# GSM.net
KiCad netlist of a schematic drawn in Altium Designer
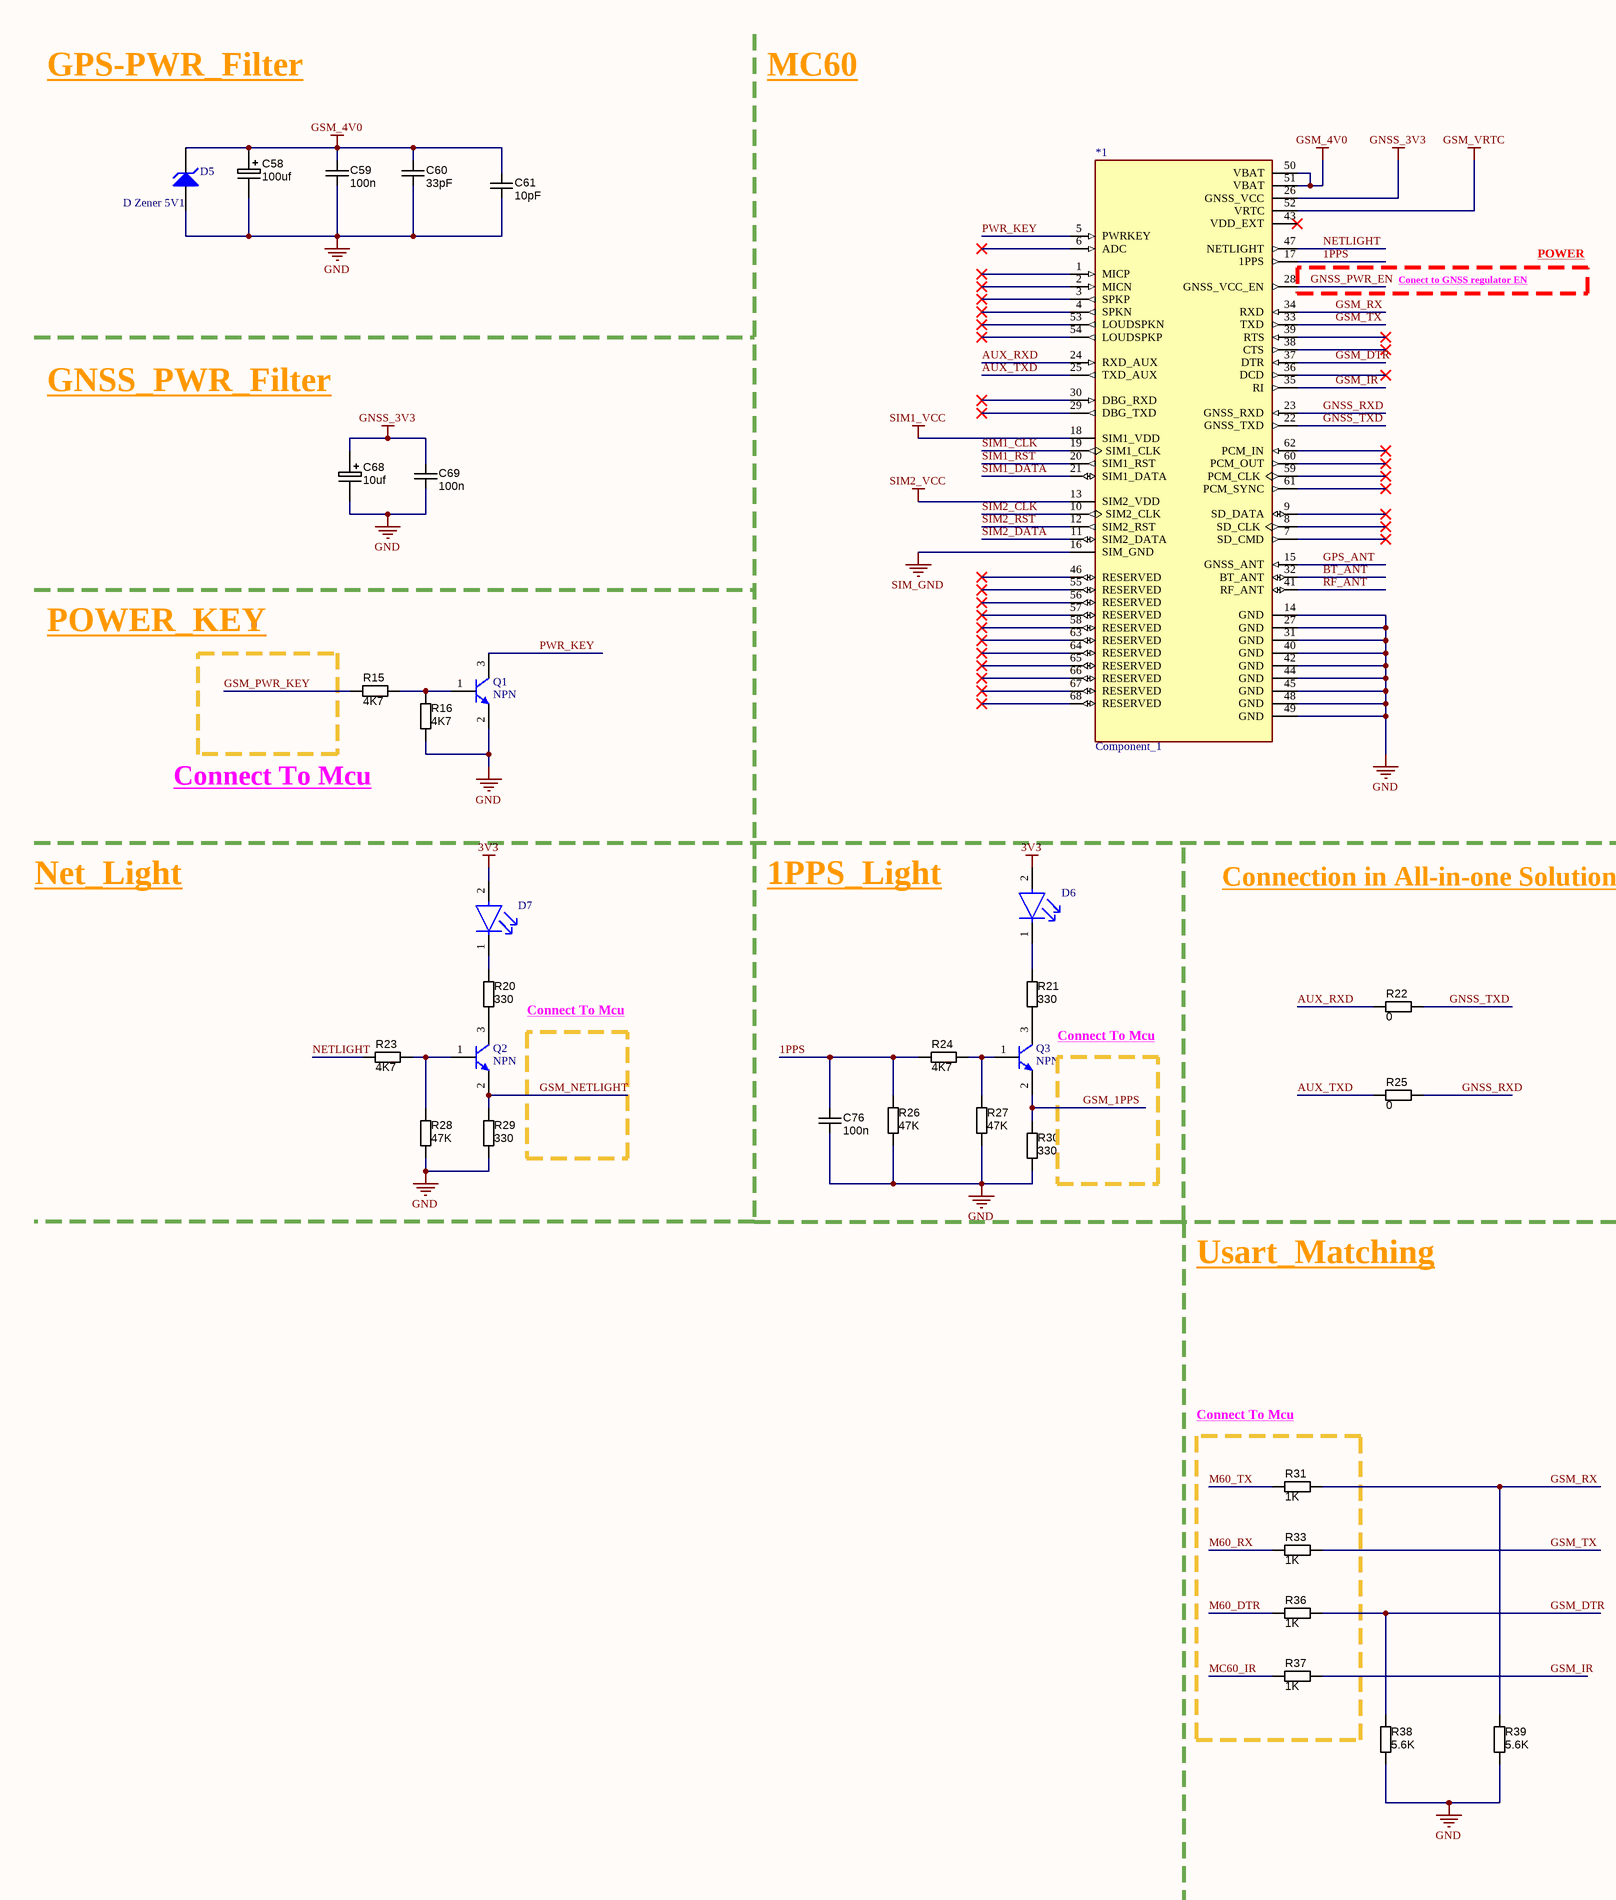
[diagram p0: GSM.SchDoc, left]
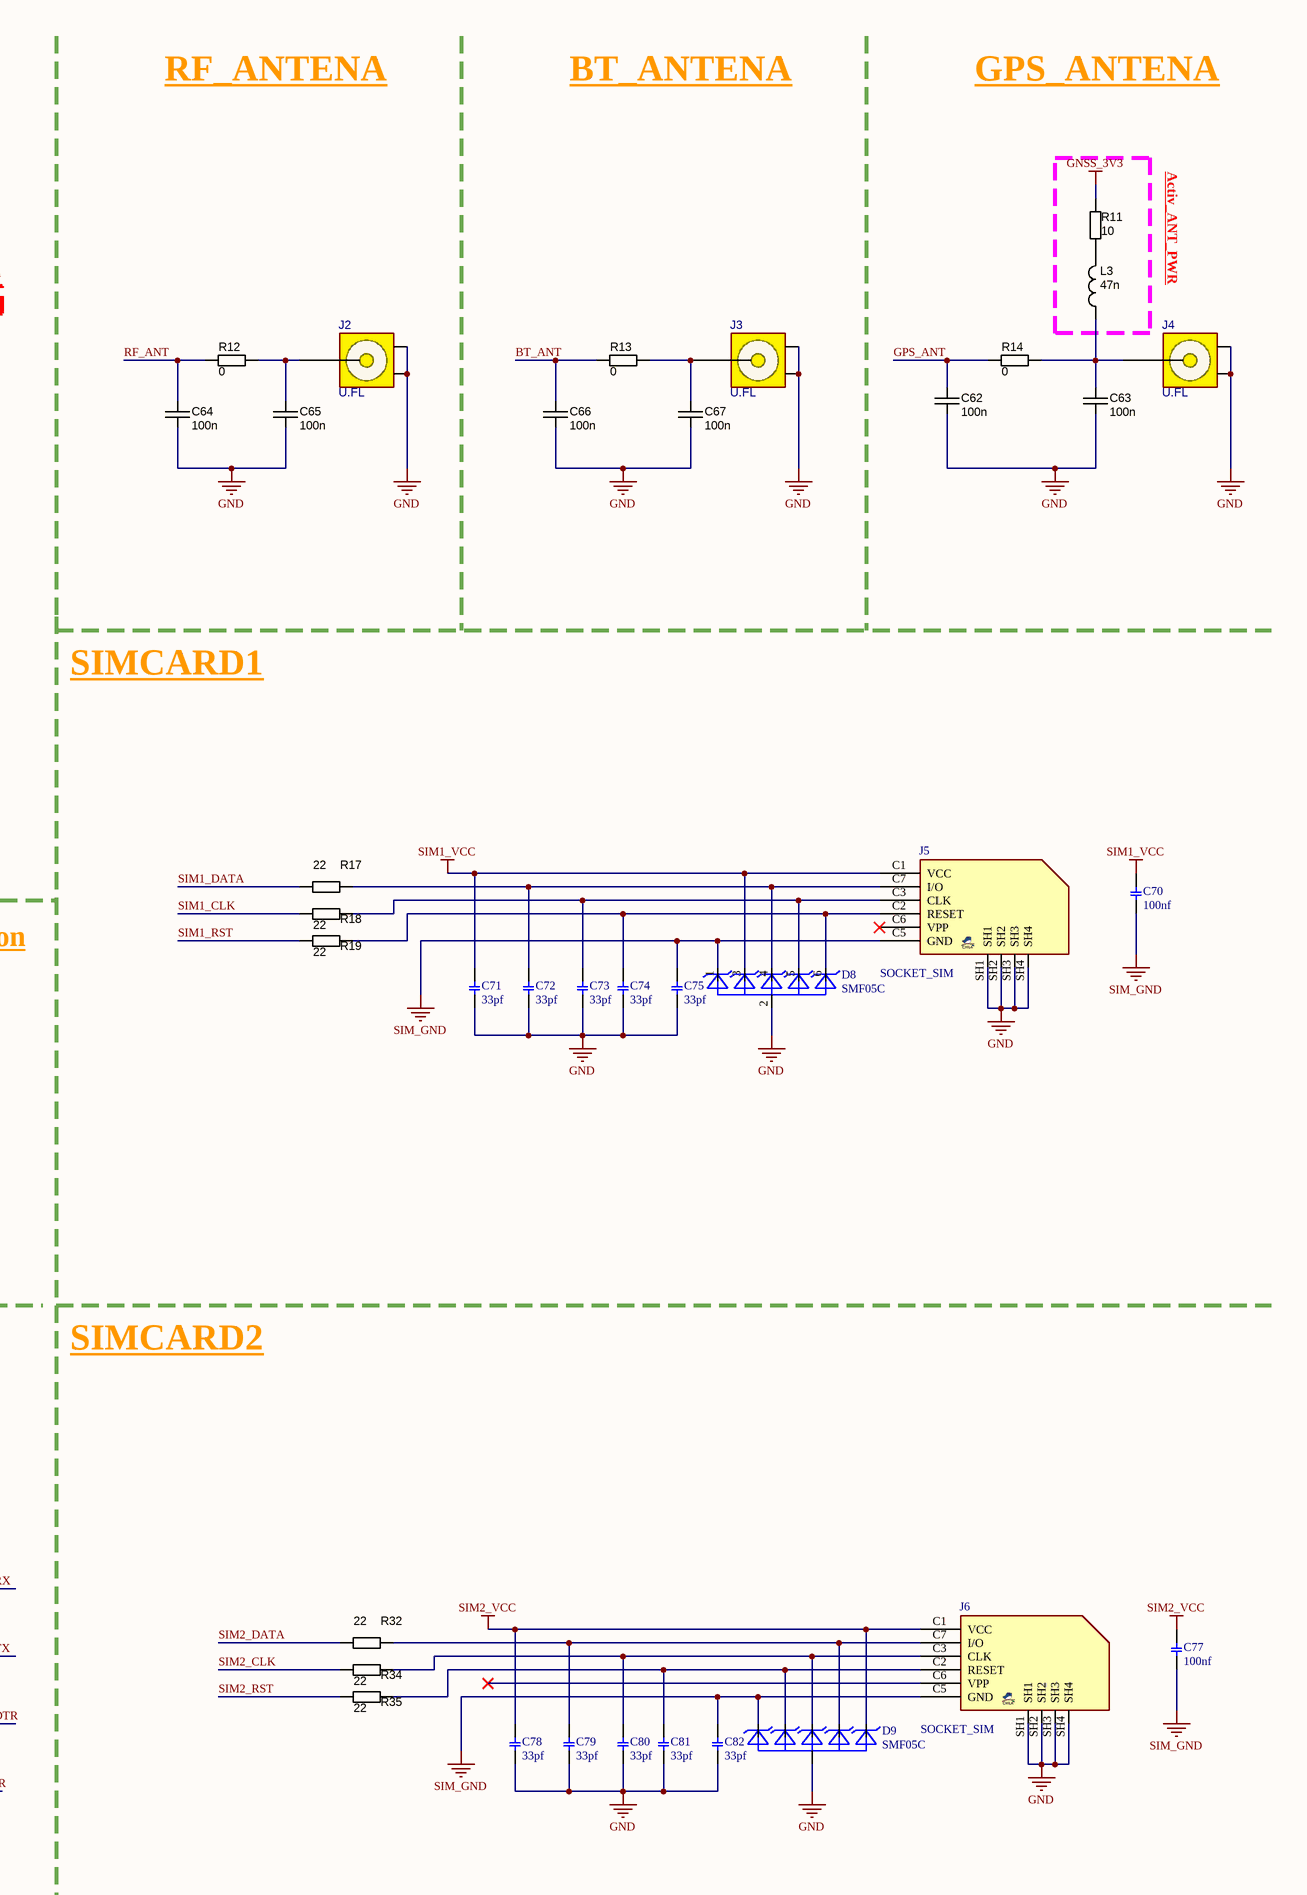
[diagram p1: GSM.SchDoc, right]

(export (version "E")
  (design (tool "Eeschema 10.0.6"))
  (components
    (comp (ref "*1")
      (value "Component_1")
      (footprint "PCBComponent_1")
      (libsource (lib "Integrated_Library1") (part "Component_1"))
    )
    (comp (ref "C58")
      (value "100uf")
      (footprint "C_TN_3528")
      (description "Capacitor SMD Tantalum 100uF 10% 16V 3216-18")
      (fields (field (name "TOLERANCE") "±10%"))
      (libsource (lib "PBL - Capacitors") (part "CAPT_4u7_3216_16V"))
    )
    (comp (ref "C59")
      (value "100n")
      (footprint "CAPC1608X90N")
      (description "Capacitor SMD Cer 100nF 10% 50V X7R 0603")
      (fields (field (name "TOLERANCE") "±10%") (field (name "Comment") "approved sub OK"))
      (libsource (lib "PBL - Capacitors") (part "CAPC_100n_0603_X7R_50V_10%"))
    )
    (comp (ref "C60")
      (value "33pF")
      (footprint "CAPC1608X90N")
      (description "Capacitor SMD Cer 33pF10% 50V X7R 0603")
      (fields (field (name "TOLERANCE") "±10%") (field (name "Comment") "approved sub OK"))
      (libsource (lib "PBL - Capacitors") (part "CAPC_100n_0603_X7R_50V_10%"))
    )
    (comp (ref "C61")
      (value "10pF")
      (footprint "CAPC1608X90N")
      (description "Capacitor SMD Cer 10pF10% 50V X7R 0603")
      (fields (field (name "TOLERANCE") "±10%") (field (name "Comment") "approved sub OK"))
      (libsource (lib "PBL - Capacitors") (part "CAPC_100n_0603_X7R_50V_10%"))
    )
    (comp (ref "C62")
      (value "100n")
      (footprint "C0402")
      (description "Capacitor SMD Cer 100nF 10% 50V X7R 0603")
      (fields (field (name "TOLERANCE") "±10%") (field (name "Comment") "approved sub OK"))
      (libsource (lib "PBL - Capacitors") (part "CAPC_100n_0603_X7R_50V_10%"))
    )
    (comp (ref "C63")
      (value "100n")
      (footprint "C0402")
      (description "Capacitor SMD Cer 100nF 10% 50V X7R 0603")
      (fields (field (name "TOLERANCE") "±10%") (field (name "Comment") "approved sub OK"))
      (libsource (lib "PBL - Capacitors") (part "CAPC_100n_0603_X7R_50V_10%"))
    )
    (comp (ref "C64")
      (value "100n")
      (footprint "C0402")
      (description "Capacitor SMD Cer 100nF 10% 50V X7R 0603")
      (fields (field (name "TOLERANCE") "±10%") (field (name "Comment") "approved sub OK"))
      (libsource (lib "PBL - Capacitors") (part "CAPC_100n_0603_X7R_50V_10%"))
    )
    (comp (ref "C65")
      (value "100n")
      (footprint "C0402")
      (description "Capacitor SMD Cer 100nF 10% 50V X7R 0603")
      (fields (field (name "TOLERANCE") "±10%") (field (name "Comment") "approved sub OK"))
      (libsource (lib "PBL - Capacitors") (part "CAPC_100n_0603_X7R_50V_10%"))
    )
    (comp (ref "C66")
      (value "100n")
      (footprint "C0402")
      (description "Capacitor SMD Cer 100nF 10% 50V X7R 0603")
      (fields (field (name "TOLERANCE") "±10%") (field (name "Comment") "approved sub OK"))
      (libsource (lib "PBL - Capacitors") (part "CAPC_100n_0603_X7R_50V_10%"))
    )
    (comp (ref "C67")
      (value "100n")
      (footprint "C0402")
      (description "Capacitor SMD Cer 100nF 10% 50V X7R 0603")
      (fields (field (name "TOLERANCE") "±10%") (field (name "Comment") "approved sub OK"))
      (libsource (lib "PBL - Capacitors") (part "CAPC_100n_0603_X7R_50V_10%"))
    )
    (comp (ref "C68")
      (value "10uf")
      (footprint "C_TN_3528")
      (description "Capacitor SMD Tantalum 10uF 10% 16V 3216-18")
      (fields (field (name "TOLERANCE") "±10%"))
      (libsource (lib "PBL - Capacitors") (part "CAPT_4u7_3216_16V"))
    )
    (comp (ref "C69")
      (value "100n")
      (footprint "CAPC1608X90N")
      (description "Capacitor SMD Cer 100nF 10% 50V X7R 0603")
      (fields (field (name "TOLERANCE") "±10%") (field (name "Comment") "approved sub OK"))
      (libsource (lib "PBL - Capacitors") (part "CAPC_100n_0603_X7R_50V_10%"))
    )
    (comp (ref "C70")
      (value "100nf")
      (footprint "0603")
      (description "Capacitor C SMD 0603")
      (libsource (lib "Capacitor") (part "Capacitor C SMD 0603"))
    )
    (comp (ref "C71")
      (value "33pf")
      (footprint "0603")
      (description "Capacitor C SMD 0603")
      (libsource (lib "Capacitor") (part "Capacitor C SMD 0603"))
    )
    (comp (ref "C72")
      (value "33pf")
      (footprint "0603")
      (description "Capacitor C SMD 0603")
      (libsource (lib "Capacitor") (part "Capacitor C SMD 0603"))
    )
    (comp (ref "C73")
      (value "33pf")
      (footprint "0603")
      (description "Capacitor C SMD 0603")
      (libsource (lib "Capacitor") (part "Capacitor C SMD 0603"))
    )
    (comp (ref "C74")
      (value "33pf")
      (footprint "0603")
      (description "Capacitor C SMD 0603")
      (libsource (lib "Capacitor") (part "Capacitor C SMD 0603"))
    )
    (comp (ref "C75")
      (value "33pf")
      (footprint "0603")
      (description "Capacitor C SMD 0603")
      (libsource (lib "Capacitor") (part "Capacitor C SMD 0603"))
    )
    (comp (ref "C76")
      (value "100n")
      (footprint "CAPC1608X90N")
      (description "Capacitor SMD Cer 100nF 10% 50V X7R 0603")
      (fields (field (name "TOLERANCE") "±10%") (field (name "Comment") "approved sub OK"))
      (libsource (lib "PBL - Capacitors") (part "CAPC_100n_0603_X7R_50V_10%"))
    )
    (comp (ref "C77")
      (value "100nf")
      (footprint "0603")
      (description "Capacitor C SMD 0603")
      (libsource (lib "Capacitor") (part "Capacitor C SMD 0603"))
    )
    (comp (ref "C78")
      (value "33pf")
      (footprint "0603")
      (description "Capacitor C SMD 0603")
      (libsource (lib "Capacitor") (part "Capacitor C SMD 0603"))
    )
    (comp (ref "C79")
      (value "33pf")
      (footprint "0603")
      (description "Capacitor C SMD 0603")
      (libsource (lib "Capacitor") (part "Capacitor C SMD 0603"))
    )
    (comp (ref "C80")
      (value "33pf")
      (footprint "0603")
      (description "Capacitor C SMD 0603")
      (libsource (lib "Capacitor") (part "Capacitor C SMD 0603"))
    )
    (comp (ref "C81")
      (value "33pf")
      (footprint "0603")
      (description "Capacitor C SMD 0603")
      (libsource (lib "Capacitor") (part "Capacitor C SMD 0603"))
    )
    (comp (ref "C82")
      (value "33pf")
      (footprint "0603")
      (description "Capacitor C SMD 0603")
      (libsource (lib "Capacitor") (part "Capacitor C SMD 0603"))
    )
    (comp (ref "D5")
      (value "D Zener 5V1")
      (footprint "DIODE-0.7")
      (description "Zener Diode")
      (fields (field (name "PUBLISHER") "Altium Limited"))
      (libsource (lib "Miscellaneous Devices") (part "D Zener"))
    )
    (comp (ref "D6")
      (value "LTST-C191TBKT")
      (footprint "FP-LTST-C191TBKT-MFG")
      (description "LED BLUE CLEAR CHIP SMD")
      (libsource (lib "Altium Content Vault") (part "8706943c75ba83719d021d2fdc84c58"))
    )
    (comp (ref "D7")
      (value "LTST-C191TBKT")
      (footprint "FP-LTST-C191TBKT-MFG")
      (description "LED BLUE CLEAR CHIP SMD")
      (libsource (lib "Altium Content Vault") (part "8706943c75ba83719d021d2fdc84c58"))
    )
    (comp (ref "D8")
      (value "SMF05C")
      (footprint "SC70-6")
      (description "12.5V Clamp 8A _8/20Âµs_ Ipp Tvs Diode Surface Mount SC-88/SC70-6/SOT-363")
      (fields (field (name "MF") "ON Semiconductor"))
      (libsource (lib "") (part "SMF05C_1"))
    )
    (comp (ref "D9")
      (value "SMF05C")
      (footprint "SC70-6")
      (description "12.5V Clamp 8A _8/20Âµs_ Ipp Tvs Diode Surface Mount SC-88/SC70-6/SOT-363")
      (fields (field (name "MF") "ON Semiconductor"))
      (libsource (lib "SMF05C") (part "SMF05C"))
    )
    (comp (ref "J2")
      (value "U.FL")
      (footprint "UFL")
      (description "CONN, RF, U.FL, STRAIGHT, Ultra Miniature Coaxial")
      (fields
        (field (name "MANF_P#") "CONUFL001-SMD, U.FL-R-SMT-1(10), 128-0711-201")
        (field (name "MANF") "Linx, Hirose, Cinch")
      )
      (libsource (lib "conn_rf") (part "CONN_RF_UFL"))
    )
    (comp (ref "J3")
      (value "U.FL")
      (footprint "UFL")
      (description "CONN, RF, U.FL, STRAIGHT, Ultra Miniature Coaxial")
      (fields
        (field (name "MANF_P#") "CONUFL001-SMD, U.FL-R-SMT-1(10), 128-0711-201")
        (field (name "MANF") "Linx, Hirose, Cinch")
      )
      (libsource (lib "conn_rf") (part "CONN_RF_UFL"))
    )
    (comp (ref "J4")
      (value "U.FL")
      (footprint "UFL")
      (description "CONN, RF, U.FL, STRAIGHT, Ultra Miniature Coaxial")
      (fields
        (field (name "MANF_P#") "CONUFL001-SMD, U.FL-R-SMT-1(10), 128-0711-201")
        (field (name "MANF") "Linx, Hirose, Cinch")
      )
      (libsource (lib "conn_rf") (part "CONN_RF_UFL"))
    )
    (comp (ref "J5")
      (value "SOCKET_SIM")
      (footprint "SIM_MICRO_GCT")
      (description "SOCKET, SIM MICRO")
      (libsource (lib "socket_card") (part "SIM_MICRO_6"))
    )
    (comp (ref "J6")
      (value "SOCKET_SIM")
      (footprint "SIM_MICRO_GCT")
      (description "SOCKET, SIM MICRO")
      (libsource (lib "socket_card") (part "SIM_MICRO_6"))
    )
    (comp (ref "L3")
      (value "47n")
      (footprint "L0603")
      (description "Inductor SMD Low DCR 47 nH 900mA 20% 1210")
      (fields (field (name "TOLERANCE") "±20%"))
      (libsource (lib "PBL - Inductors") (part "INDC_10u_LowRDC"))
    )
    (comp (ref "Q1")
      (value "NPN")
      (footprint "SOT23-3")
      (description "NPN Bipolar Transistor")
      (fields (field (name "PUBLISHER") "Altium Limited"))
      (libsource (lib "Miscellaneous Devices") (part "NPN"))
    )
    (comp (ref "Q2")
      (value "NPN")
      (footprint "SOT23-3")
      (description "NPN Bipolar Transistor")
      (fields (field (name "PUBLISHER") "Altium Limited"))
      (libsource (lib "Miscellaneous Devices") (part "NPN"))
    )
    (comp (ref "Q3")
      (value "NPN")
      (footprint "SOT23-3")
      (description "NPN Bipolar Transistor")
      (fields (field (name "PUBLISHER") "Altium Limited"))
      (libsource (lib "Miscellaneous Devices") (part "NPN"))
    )
    (comp (ref "R11")
      (value "10")
      (footprint "0402")
      (description "Resistor SMD chip 10 Ohm 0.1W 5% 0603")
      (fields (field (name "TOLERANCE") "±5%") (field (name "Comment") "Thick Film"))
      (libsource (lib "") (part "RES_4K7_0603_5%_2"))
    )
    (comp (ref "R12")
      (value "0")
      (footprint "0402")
      (description "Resistor SMD chip 0 Ohm 0.1W 5% 0603")
      (fields (field (name "TOLERANCE") "±5%") (field (name "Comment") "Thick Film"))
      (libsource (lib "") (part "RES_4K7_0603_5%_1"))
    )
    (comp (ref "R13")
      (value "0")
      (footprint "0402")
      (description "Resistor SMD chip 0 Ohm 0.1W 5% 0603")
      (fields (field (name "TOLERANCE") "±5%") (field (name "Comment") "Thick Film"))
      (libsource (lib "") (part "RES_4K7_0603_5%_1"))
    )
    (comp (ref "R14")
      (value "0")
      (footprint "0402")
      (description "Resistor SMD chip 0 Ohm 0.1W 5% 0603")
      (fields (field (name "TOLERANCE") "±5%") (field (name "Comment") "Thick Film"))
      (libsource (lib "") (part "RES_4K7_0603_5%_1"))
    )
    (comp (ref "R15")
      (value "4K7")
      (footprint "RESC1608X55N")
      (description "Resistor SMD chip 4.7k Ohm 0.1W 5% 0603")
      (fields (field (name "TOLERANCE") "±5%") (field (name "Comment") "Thick Film"))
      (libsource (lib "") (part "RES_4K7_0603_5%_1"))
    )
    (comp (ref "R16")
      (value "4K7")
      (footprint "RESC1608X55N")
      (description "Resistor SMD chip 4.7k Ohm 0.1W 5% 0603")
      (fields (field (name "TOLERANCE") "±5%") (field (name "Comment") "Thick Film"))
      (libsource (lib "") (part "RES_4K7_0603_5%_2"))
    )
    (comp (ref "R17")
      (value "22")
      (footprint "RESC1608X55N")
      (description "Resistor SMD chip 22 Ohm 0.1W 5% 0603")
      (fields (field (name "TOLERANCE") "±5%") (field (name "Comment") "Thick Film"))
      (libsource (lib "PBL - Resistors") (part "RES_4K7_0603_5%"))
    )
    (comp (ref "R18")
      (value "22")
      (footprint "RESC1608X55N")
      (description "Resistor SMD chip 22 Ohm 0.1W 5% 0603")
      (fields (field (name "TOLERANCE") "±5%") (field (name "Comment") "Thick Film"))
      (libsource (lib "PBL - Resistors") (part "RES_4K7_0603_5%"))
    )
    (comp (ref "R19")
      (value "22")
      (footprint "RESC1608X55N")
      (description "Resistor SMD chip 22 Ohm 0.1W 5% 0603")
      (fields (field (name "TOLERANCE") "±5%") (field (name "Comment") "Thick Film"))
      (libsource (lib "PBL - Resistors") (part "RES_4K7_0603_5%"))
    )
    (comp (ref "R20")
      (value "330")
      (footprint "RESC1608X55N")
      (description "Resistor SMD chip 330 Ohm 0.1W 5% 0603")
      (fields (field (name "TOLERANCE") "±5%") (field (name "Comment") "Thick Film"))
      (libsource (lib "") (part "RES_4K7_0603_5%_2"))
    )
    (comp (ref "R21")
      (value "330")
      (footprint "RESC1608X55N")
      (description "Resistor SMD chip 330 Ohm 0.1W 5% 0603")
      (fields (field (name "TOLERANCE") "±5%") (field (name "Comment") "Thick Film"))
      (libsource (lib "") (part "RES_4K7_0603_5%_2"))
    )
    (comp (ref "R22")
      (value "0")
      (footprint "RESC1608X55N")
      (description "Resistor SMD chip 0 Ohm 0.1W 5% 0603")
      (fields (field (name "TOLERANCE") "±5%") (field (name "Comment") "Thick Film"))
      (libsource (lib "") (part "RES_4K7_0603_5%_1"))
    )
    (comp (ref "R23")
      (value "4K7")
      (footprint "RESC1608X55N")
      (description "Resistor SMD chip 4.7k Ohm 0.1W 5% 0603")
      (fields (field (name "TOLERANCE") "±5%") (field (name "Comment") "Thick Film"))
      (libsource (lib "PBL - Resistors") (part "RES_4K7_0603_5%"))
    )
    (comp (ref "R24")
      (value "4K7")
      (footprint "RESC1608X55N")
      (description "Resistor SMD chip 4.7k Ohm 0.1W 5% 0603")
      (fields (field (name "TOLERANCE") "±5%") (field (name "Comment") "Thick Film"))
      (libsource (lib "PBL - Resistors") (part "RES_4K7_0603_5%"))
    )
    (comp (ref "R25")
      (value "0")
      (footprint "RESC1608X55N")
      (description "Resistor SMD chip 0 Ohm 0.1W 5% 0603")
      (fields (field (name "TOLERANCE") "±5%") (field (name "Comment") "Thick Film"))
      (libsource (lib "") (part "RES_4K7_0603_5%_1"))
    )
    (comp (ref "R26")
      (value "47K")
      (footprint "RESC1608X55N")
      (description "Resistor SMD chip 47K Ohm 0.1W 5% 0603")
      (fields (field (name "TOLERANCE") "±5%") (field (name "Comment") "Thick Film"))
      (libsource (lib "") (part "RES_4K7_0603_5%_2"))
    )
    (comp (ref "R27")
      (value "47K")
      (footprint "RESC1608X55N")
      (description "Resistor SMD chip 47K Ohm 0.1W 5% 0603")
      (fields (field (name "TOLERANCE") "±5%") (field (name "Comment") "Thick Film"))
      (libsource (lib "") (part "RES_4K7_0603_5%_2"))
    )
    (comp (ref "R28")
      (value "47K")
      (footprint "RESC1608X55N")
      (description "Resistor SMD chip 47K Ohm 0.1W 5% 0603")
      (fields (field (name "TOLERANCE") "±5%") (field (name "Comment") "Thick Film"))
      (libsource (lib "") (part "RES_4K7_0603_5%_2"))
    )
    (comp (ref "R29")
      (value "330")
      (footprint "RESC1608X55N")
      (description "Resistor SMD chip 330 Ohm 0.1W 5% 0603")
      (fields (field (name "TOLERANCE") "±5%") (field (name "Comment") "Thick Film"))
      (libsource (lib "") (part "RES_4K7_0603_5%_2"))
    )
    (comp (ref "R30")
      (value "330")
      (footprint "RESC1608X55N")
      (description "Resistor SMD chip 330 Ohm 0.1W 5% 0603")
      (fields (field (name "TOLERANCE") "±5%") (field (name "Comment") "Thick Film"))
      (libsource (lib "") (part "RES_4K7_0603_5%_2"))
    )
    (comp (ref "R31")
      (value "1K")
      (footprint "RESC1608X55N")
      (description "Resistor SMD chip 1K Ohm 0.1W 5% 0603")
      (fields (field (name "TOLERANCE") "±5%") (field (name "Comment") "Thick Film"))
      (libsource (lib "") (part "RES_4K7_0603_5%_1"))
    )
    (comp (ref "R32")
      (value "22")
      (footprint "RESC1608X55N")
      (description "Resistor SMD chip 22 Ohm 0.1W 5% 0603")
      (fields (field (name "TOLERANCE") "±5%") (field (name "Comment") "Thick Film"))
      (libsource (lib "PBL - Resistors") (part "RES_4K7_0603_5%"))
    )
    (comp (ref "R33")
      (value "1K")
      (footprint "RESC1608X55N")
      (description "Resistor SMD chip 1K Ohm 0.1W 5% 0603")
      (fields (field (name "TOLERANCE") "±5%") (field (name "Comment") "Thick Film"))
      (libsource (lib "") (part "RES_4K7_0603_5%_1"))
    )
    (comp (ref "R34")
      (value "22")
      (footprint "RESC1608X55N")
      (description "Resistor SMD chip 22 Ohm 0.1W 5% 0603")
      (fields (field (name "TOLERANCE") "±5%") (field (name "Comment") "Thick Film"))
      (libsource (lib "PBL - Resistors") (part "RES_4K7_0603_5%"))
    )
    (comp (ref "R35")
      (value "22")
      (footprint "RESC1608X55N")
      (description "Resistor SMD chip 22 Ohm 0.1W 5% 0603")
      (fields (field (name "TOLERANCE") "±5%") (field (name "Comment") "Thick Film"))
      (libsource (lib "PBL - Resistors") (part "RES_4K7_0603_5%"))
    )
    (comp (ref "R36")
      (value "1K")
      (footprint "RESC1608X55N")
      (description "Resistor SMD chip 1K Ohm 0.1W 5% 0603")
      (fields (field (name "TOLERANCE") "±5%") (field (name "Comment") "Thick Film"))
      (libsource (lib "") (part "RES_4K7_0603_5%_1"))
    )
    (comp (ref "R37")
      (value "1K")
      (footprint "RESC1608X55N")
      (description "Resistor SMD chip 1K Ohm 0.1W 5% 0603")
      (fields (field (name "TOLERANCE") "±5%") (field (name "Comment") "Thick Film"))
      (libsource (lib "") (part "RES_4K7_0603_5%_1"))
    )
    (comp (ref "R38")
      (value "5.6K")
      (footprint "RESC1608X55N")
      (description "Resistor SMD chip 5.6K Ohm 0.1W 5% 0603")
      (fields (field (name "TOLERANCE") "±5%") (field (name "Comment") "Thick Film"))
      (libsource (lib "") (part "RES_4K7_0603_5%_2"))
    )
    (comp (ref "R39")
      (value "5.6K")
      (footprint "RESC1608X55N")
      (description "Resistor SMD chip 5.6K Ohm 0.1W 5% 0603")
      (fields (field (name "TOLERANCE") "±5%") (field (name "Comment") "Thick Film"))
      (libsource (lib "") (part "RES_4K7_0603_5%_2"))
    )
  )
  (nets
    (net (code "1") (name "/1PPS") (class "Default")
      (node (ref "*1") (pin "17") (pinfunction "1PPS_17") (pintype "output"))
      (node (ref "C76") (pin "1") (pintype "passive"))
      (node (ref "R24") (pin "1") (pinfunction "1_1") (pintype "passive"))
      (node (ref "R26") (pin "1") (pinfunction "1_1") (pintype "passive"))
    )
    (net (code "2") (name "/AUX_RXD") (class "Default")
      (node (ref "*1") (pin "24") (pinfunction "RXD_AUX_24") (pintype "input"))
      (node (ref "R22") (pin "2") (pinfunction "2_2") (pintype "passive"))
    )
    (net (code "3") (name "/AUX_TXD") (class "Default")
      (node (ref "*1") (pin "25") (pinfunction "TXD_AUX_25") (pintype "output"))
      (node (ref "R25") (pin "2") (pinfunction "2_2") (pintype "passive"))
    )
    (net (code "4") (name "/BT_ANT") (class "Default")
      (node (ref "*1") (pin "32") (pinfunction "BT_ANT_32") (pintype "bidirectional"))
      (node (ref "C66") (pin "1") (pintype "passive"))
      (node (ref "R13") (pin "2") (pinfunction "2_2") (pintype "passive"))
    )
    (net (code "5") (name "/GNSS_PWR_EN") (class "Default")
      (node (ref "*1") (pin "28") (pinfunction "GNSS_VCC_EN_28") (pintype "output"))
    )
    (net (code "6") (name "/GNSS_RXD") (class "Default")
      (node (ref "*1") (pin "23") (pinfunction "GNSS_RXD_23") (pintype "input"))
      (node (ref "R25") (pin "1") (pinfunction "1_1") (pintype "passive"))
    )
    (net (code "7") (name "/GNSS_TXD") (class "Default")
      (node (ref "*1") (pin "22") (pinfunction "GNSS_TXD_22") (pintype "output"))
      (node (ref "R22") (pin "1") (pinfunction "1_1") (pintype "passive"))
    )
    (net (code "8") (name "/GPS_ANT") (class "Default")
      (node (ref "*1") (pin "15") (pinfunction "GNSS_ANT_15") (pintype "input"))
      (node (ref "C62") (pin "1") (pintype "passive"))
      (node (ref "R14") (pin "2") (pinfunction "2_2") (pintype "passive"))
    )
    (net (code "9") (name "/GSM_1PPS") (class "Default")
      (node (ref "Q3") (pin "2") (pinfunction "E_2") (pintype "passive"))
      (node (ref "R30") (pin "1") (pinfunction "1_1") (pintype "passive"))
    )
    (net (code "10") (name "/GSM_DTR") (class "Default")
      (node (ref "*1") (pin "37") (pinfunction "DTR_37") (pintype "input"))
      (node (ref "R36") (pin "1") (pinfunction "1_1") (pintype "passive"))
      (node (ref "R38") (pin "1") (pinfunction "1_1") (pintype "passive"))
    )
    (net (code "11") (name "/GSM_IR") (class "Default")
      (node (ref "*1") (pin "35") (pinfunction "RI_35") (pintype "output"))
      (node (ref "R37") (pin "1") (pinfunction "1_1") (pintype "passive"))
    )
    (net (code "12") (name "/GSM_NETLIGHT") (class "Default")
      (node (ref "Q2") (pin "2") (pinfunction "E_2") (pintype "passive"))
      (node (ref "R29") (pin "1") (pinfunction "1_1") (pintype "passive"))
    )
    (net (code "13") (name "/GSM_PWR_KEY") (class "Default")
      (node (ref "R15") (pin "2") (pinfunction "2_2") (pintype "passive"))
    )
    (net (code "14") (name "/GSM_RX") (class "Default")
      (node (ref "*1") (pin "34") (pinfunction "RXD_34") (pintype "input"))
      (node (ref "R31") (pin "1") (pinfunction "1_1") (pintype "passive"))
      (node (ref "R39") (pin "1") (pinfunction "1_1") (pintype "passive"))
    )
    (net (code "15") (name "/GSM_TX") (class "Default")
      (node (ref "*1") (pin "33") (pinfunction "TXD_33") (pintype "output"))
      (node (ref "R33") (pin "1") (pinfunction "1_1") (pintype "passive"))
    )
    (net (code "16") (name "/M60_DTR") (class "Default")
      (node (ref "R36") (pin "2") (pinfunction "2_2") (pintype "passive"))
    )
    (net (code "17") (name "/M60_RX") (class "Default")
      (node (ref "R33") (pin "2") (pinfunction "2_2") (pintype "passive"))
    )
    (net (code "18") (name "/M60_TX") (class "Default")
      (node (ref "R31") (pin "2") (pinfunction "2_2") (pintype "passive"))
    )
    (net (code "19") (name "/MC60_IR") (class "Default")
      (node (ref "R37") (pin "2") (pinfunction "2_2") (pintype "passive"))
    )
    (net (code "20") (name "/NETLIGHT") (class "Default")
      (node (ref "*1") (pin "47") (pinfunction "NETLIGHT_47") (pintype "output"))
      (node (ref "R23") (pin "1") (pinfunction "1_1") (pintype "passive"))
    )
    (net (code "21") (name "/PWR_KEY") (class "Default")
      (node (ref "*1") (pin "5") (pinfunction "PWRKEY_5") (pintype "input"))
      (node (ref "Q1") (pin "3") (pinfunction "C_3") (pintype "passive"))
    )
    (net (code "22") (name "/RF_ANT") (class "Default")
      (node (ref "*1") (pin "41") (pinfunction "RF_ANT_41") (pintype "bidirectional"))
      (node (ref "C64") (pin "1") (pintype "passive"))
      (node (ref "R12") (pin "2") (pinfunction "2_2") (pintype "passive"))
    )
    (net (code "23") (name "/SIM1_CLK") (class "Default")
      (node (ref "*1") (pin "19") (pinfunction "SIM1_CLK_19") (pintype "output"))
      (node (ref "R18") (pin "1") (pinfunction "1_1") (pintype "passive"))
    )
    (net (code "24") (name "/SIM1_DATA") (class "Default")
      (node (ref "*1") (pin "21") (pinfunction "SIM1_DATA_21") (pintype "bidirectional"))
      (node (ref "R17") (pin "1") (pinfunction "1_1") (pintype "passive"))
    )
    (net (code "25") (name "/SIM1_RST") (class "Default")
      (node (ref "*1") (pin "20") (pinfunction "SIM1_RST_20") (pintype "output"))
      (node (ref "R19") (pin "1") (pinfunction "1_1") (pintype "passive"))
    )
    (net (code "26") (name "/SIM2_CLK") (class "Default")
      (node (ref "*1") (pin "10") (pinfunction "SIM2_CLK_10") (pintype "output"))
      (node (ref "R34") (pin "1") (pinfunction "1_1") (pintype "passive"))
    )
    (net (code "27") (name "/SIM2_DATA") (class "Default")
      (node (ref "*1") (pin "11") (pinfunction "SIM2_DATA_11") (pintype "bidirectional"))
      (node (ref "R32") (pin "1") (pinfunction "1_1") (pintype "passive"))
    )
    (net (code "28") (name "/SIM2_RST") (class "Default")
      (node (ref "*1") (pin "12") (pinfunction "SIM2_RST_12") (pintype "output"))
      (node (ref "R35") (pin "1") (pinfunction "1_1") (pintype "passive"))
    )
    (net (code "29") (name "3V3") (class "Default")
      (node (ref "D6") (pin "2") (pinfunction "A_2") (pintype "passive"))
      (node (ref "D7") (pin "2") (pinfunction "A_2") (pintype "passive"))
    )
    (net (code "30") (name "GND") (class "Default")
      (node (ref "*1") (pin "14") (pinfunction "GND_14") (pintype "power_in"))
      (node (ref "*1") (pin "27") (pinfunction "GND_27") (pintype "power_in"))
      (node (ref "*1") (pin "31") (pinfunction "GND_31") (pintype "power_in"))
      (node (ref "*1") (pin "40") (pinfunction "GND_40") (pintype "power_in"))
      (node (ref "*1") (pin "42") (pinfunction "GND_42") (pintype "power_in"))
      (node (ref "*1") (pin "44") (pinfunction "GND_44") (pintype "power_in"))
      (node (ref "*1") (pin "45") (pinfunction "GND_45") (pintype "power_in"))
      (node (ref "*1") (pin "48") (pinfunction "GND_48") (pintype "power_in"))
      (node (ref "*1") (pin "49") (pinfunction "GND_49") (pintype "power_in"))
      (node (ref "C58") (pin "2") (pintype "passive"))
      (node (ref "C59") (pin "2") (pintype "passive"))
      (node (ref "C60") (pin "2") (pintype "passive"))
      (node (ref "C61") (pin "2") (pintype "passive"))
      (node (ref "C62") (pin "2") (pintype "passive"))
      (node (ref "C63") (pin "2") (pintype "passive"))
      (node (ref "C64") (pin "2") (pintype "passive"))
      (node (ref "C65") (pin "2") (pintype "passive"))
      (node (ref "C66") (pin "2") (pintype "passive"))
      (node (ref "C67") (pin "2") (pintype "passive"))
      (node (ref "C68") (pin "2") (pintype "passive"))
      (node (ref "C69") (pin "2") (pintype "passive"))
      (node (ref "C71") (pin "1") (pinfunction "1_1") (pintype "passive"))
      (node (ref "C72") (pin "1") (pinfunction "1_1") (pintype "passive"))
      (node (ref "C73") (pin "1") (pinfunction "1_1") (pintype "passive"))
      (node (ref "C74") (pin "1") (pinfunction "1_1") (pintype "passive"))
      (node (ref "C75") (pin "1") (pinfunction "1_1") (pintype "passive"))
      (node (ref "C76") (pin "2") (pintype "passive"))
      (node (ref "C78") (pin "1") (pinfunction "1_1") (pintype "passive"))
      (node (ref "C79") (pin "1") (pinfunction "1_1") (pintype "passive"))
      (node (ref "C80") (pin "1") (pinfunction "1_1") (pintype "passive"))
      (node (ref "C81") (pin "1") (pinfunction "1_1") (pintype "passive"))
      (node (ref "C82") (pin "1") (pinfunction "1_1") (pintype "passive"))
      (node (ref "D5") (pin "1") (pinfunction "A_1") (pintype "passive"))
      (node (ref "D8") (pin "2") (pinfunction "A_2") (pintype "passive"))
      (node (ref "D9") (pin "2") (pinfunction "A_2") (pintype "passive"))
      (node (ref "J2") (pin "2") (pinfunction "G1_2") (pintype "passive"))
      (node (ref "J2") (pin "3") (pinfunction "G2_3") (pintype "passive"))
      (node (ref "J3") (pin "2") (pinfunction "G1_2") (pintype "passive"))
      (node (ref "J3") (pin "3") (pinfunction "G2_3") (pintype "passive"))
      (node (ref "J4") (pin "2") (pinfunction "G1_2") (pintype "passive"))
      (node (ref "J4") (pin "3") (pinfunction "G2_3") (pintype "passive"))
      (node (ref "J5") (pin "SH1") (pinfunction "SH1_SH1") (pintype "passive"))
      (node (ref "J5") (pin "SH2") (pinfunction "SH2_SH2") (pintype "passive"))
      (node (ref "J5") (pin "SH3") (pinfunction "SH3_SH3") (pintype "passive"))
      (node (ref "J5") (pin "SH4") (pinfunction "SH4_SH4") (pintype "passive"))
      (node (ref "J6") (pin "SH1") (pinfunction "SH1_SH1") (pintype "passive"))
      (node (ref "J6") (pin "SH2") (pinfunction "SH2_SH2") (pintype "passive"))
      (node (ref "J6") (pin "SH3") (pinfunction "SH3_SH3") (pintype "passive"))
      (node (ref "J6") (pin "SH4") (pinfunction "SH4_SH4") (pintype "passive"))
      (node (ref "Q1") (pin "2") (pinfunction "E_2") (pintype "passive"))
      (node (ref "R16") (pin "2") (pinfunction "2_2") (pintype "passive"))
      (node (ref "R26") (pin "2") (pinfunction "2_2") (pintype "passive"))
      (node (ref "R27") (pin "2") (pinfunction "2_2") (pintype "passive"))
      (node (ref "R28") (pin "2") (pinfunction "2_2") (pintype "passive"))
      (node (ref "R29") (pin "2") (pinfunction "2_2") (pintype "passive"))
      (node (ref "R30") (pin "2") (pinfunction "2_2") (pintype "passive"))
      (node (ref "R38") (pin "2") (pinfunction "2_2") (pintype "passive"))
      (node (ref "R39") (pin "2") (pinfunction "2_2") (pintype "passive"))
    )
    (net (code "31") (name "GNSS_3V3") (class "Default")
      (node (ref "*1") (pin "26") (pinfunction "GNSS_VCC_26") (pintype "power_in"))
      (node (ref "C68") (pin "1") (pintype "passive"))
      (node (ref "C69") (pin "1") (pintype "passive"))
      (node (ref "R11") (pin "1") (pinfunction "1_1") (pintype "passive"))
    )
    (net (code "32") (name "GSM_4V0") (class "Default")
      (node (ref "*1") (pin "50") (pinfunction "VBAT_50") (pintype "power_in"))
      (node (ref "*1") (pin "51") (pinfunction "VBAT_51") (pintype "power_in"))
      (node (ref "C58") (pin "1") (pintype "passive"))
      (node (ref "C59") (pin "1") (pintype "passive"))
      (node (ref "C60") (pin "1") (pintype "passive"))
      (node (ref "C61") (pin "1") (pintype "passive"))
      (node (ref "D5") (pin "2") (pinfunction "K_2") (pintype "passive"))
    )
    (net (code "33") (name "GSM_VRTC") (class "Default")
      (node (ref "*1") (pin "52") (pinfunction "VRTC_52") (pintype "power_in"))
    )
    (net (code "34") (name "Net-(D6-C)") (class "Default")
      (node (ref "D6") (pin "1") (pinfunction "C_1") (pintype "passive"))
      (node (ref "R21") (pin "1") (pinfunction "1_1") (pintype "passive"))
    )
    (net (code "35") (name "Net-(D7-C)") (class "Default")
      (node (ref "D7") (pin "1") (pinfunction "C_1") (pintype "passive"))
      (node (ref "R20") (pin "1") (pinfunction "1_1") (pintype "passive"))
    )
    (net (code "36") (name "Net-(D8-C3)") (class "Default")
      (node (ref "C72") (pin "2") (pinfunction "2_2") (pintype "passive"))
      (node (ref "D8") (pin "4") (pinfunction "C3_4") (pintype "passive"))
      (node (ref "J5") (pin "C7") (pinfunction "I/O_C7") (pintype "passive"))
      (node (ref "R17") (pin "2") (pinfunction "2_2") (pintype "passive"))
    )
    (net (code "37") (name "Net-(D8-C4)") (class "Default")
      (node (ref "C73") (pin "2") (pinfunction "2_2") (pintype "passive"))
      (node (ref "D8") (pin "5") (pinfunction "C4_5") (pintype "passive"))
      (node (ref "J5") (pin "C3") (pinfunction "CLK_C3") (pintype "passive"))
      (node (ref "R18") (pin "2") (pinfunction "2_2") (pintype "passive"))
    )
    (net (code "38") (name "Net-(D8-C5)") (class "Default")
      (node (ref "C74") (pin "2") (pinfunction "2_2") (pintype "passive"))
      (node (ref "D8") (pin "6") (pinfunction "C5_6") (pintype "passive"))
      (node (ref "J5") (pin "C2") (pinfunction "RESET_C2") (pintype "passive"))
      (node (ref "R19") (pin "2") (pinfunction "2_2") (pintype "passive"))
    )
    (net (code "39") (name "Net-(D9-C2)") (class "Default")
      (node (ref "C81") (pin "2") (pinfunction "2_2") (pintype "passive"))
      (node (ref "D9") (pin "3") (pinfunction "C2_3") (pintype "passive"))
      (node (ref "J6") (pin "C2") (pinfunction "RESET_C2") (pintype "passive"))
      (node (ref "R35") (pin "2") (pinfunction "2_2") (pintype "passive"))
    )
    (net (code "40") (name "Net-(D9-C3)") (class "Default")
      (node (ref "C80") (pin "2") (pinfunction "2_2") (pintype "passive"))
      (node (ref "D9") (pin "4") (pinfunction "C3_4") (pintype "passive"))
      (node (ref "J6") (pin "C3") (pinfunction "CLK_C3") (pintype "passive"))
      (node (ref "R34") (pin "2") (pinfunction "2_2") (pintype "passive"))
    )
    (net (code "41") (name "Net-(D9-C4)") (class "Default")
      (node (ref "C79") (pin "2") (pinfunction "2_2") (pintype "passive"))
      (node (ref "D9") (pin "5") (pinfunction "C4_5") (pintype "passive"))
      (node (ref "J6") (pin "C7") (pinfunction "I/O_C7") (pintype "passive"))
      (node (ref "R32") (pin "2") (pinfunction "2_2") (pintype "passive"))
    )
    (net (code "42") (name "Net-(J2-SIG)") (class "Default")
      (node (ref "C65") (pin "1") (pintype "passive"))
      (node (ref "J2") (pin "1") (pinfunction "SIG_1") (pintype "passive"))
      (node (ref "R12") (pin "1") (pinfunction "1_1") (pintype "passive"))
    )
    (net (code "43") (name "Net-(J3-SIG)") (class "Default")
      (node (ref "C67") (pin "1") (pintype "passive"))
      (node (ref "J3") (pin "1") (pinfunction "SIG_1") (pintype "passive"))
      (node (ref "R13") (pin "1") (pinfunction "1_1") (pintype "passive"))
    )
    (net (code "44") (name "Net-(J4-SIG)") (class "Default")
      (node (ref "C63") (pin "1") (pintype "passive"))
      (node (ref "J4") (pin "1") (pinfunction "SIG_1") (pintype "passive"))
      (node (ref "L3") (pin "1") (pinfunction "1_1") (pintype "passive"))
      (node (ref "R14") (pin "1") (pinfunction "1_1") (pintype "passive"))
    )
    (net (code "45") (name "Net-(L3-Pad2)") (class "Default")
      (node (ref "L3") (pin "2") (pinfunction "2_2") (pintype "passive"))
      (node (ref "R11") (pin "2") (pinfunction "2_2") (pintype "passive"))
    )
    (net (code "46") (name "Net-(Q1-B)") (class "Default")
      (node (ref "Q1") (pin "1") (pinfunction "B_1") (pintype "passive"))
      (node (ref "R15") (pin "1") (pinfunction "1_1") (pintype "passive"))
      (node (ref "R16") (pin "1") (pinfunction "1_1") (pintype "passive"))
    )
    (net (code "47") (name "Net-(Q2-B)") (class "Default")
      (node (ref "Q2") (pin "1") (pinfunction "B_1") (pintype "passive"))
      (node (ref "R23") (pin "2") (pinfunction "2_2") (pintype "passive"))
      (node (ref "R28") (pin "1") (pinfunction "1_1") (pintype "passive"))
    )
    (net (code "48") (name "Net-(Q2-C)") (class "Default")
      (node (ref "Q2") (pin "3") (pinfunction "C_3") (pintype "passive"))
      (node (ref "R20") (pin "2") (pinfunction "2_2") (pintype "passive"))
    )
    (net (code "49") (name "Net-(Q3-B)") (class "Default")
      (node (ref "Q3") (pin "1") (pinfunction "B_1") (pintype "passive"))
      (node (ref "R24") (pin "2") (pinfunction "2_2") (pintype "passive"))
      (node (ref "R27") (pin "1") (pinfunction "1_1") (pintype "passive"))
    )
    (net (code "50") (name "Net-(Q3-C)") (class "Default")
      (node (ref "Q3") (pin "3") (pinfunction "C_3") (pintype "passive"))
      (node (ref "R21") (pin "2") (pinfunction "2_2") (pintype "passive"))
    )
    (net (code "51") (name "SIM1_VCC") (class "Default")
      (node (ref "*1") (pin "18") (pinfunction "SIM1_VDD_18") (pintype "power_in"))
      (node (ref "C70") (pin "2") (pinfunction "2_2") (pintype "passive"))
      (node (ref "C71") (pin "2") (pinfunction "2_2") (pintype "passive"))
      (node (ref "D8") (pin "3") (pinfunction "C2_3") (pintype "passive"))
      (node (ref "J5") (pin "C1") (pinfunction "VCC_C1") (pintype "passive"))
    )
    (net (code "52") (name "SIM2_VCC") (class "Default")
      (node (ref "*1") (pin "13") (pinfunction "SIM2_VDD_13") (pintype "power_in"))
      (node (ref "C77") (pin "2") (pinfunction "2_2") (pintype "passive"))
      (node (ref "C78") (pin "2") (pinfunction "2_2") (pintype "passive"))
      (node (ref "D9") (pin "6") (pinfunction "C5_6") (pintype "passive"))
      (node (ref "J6") (pin "C1") (pinfunction "VCC_C1") (pintype "passive"))
    )
    (net (code "53") (name "SIM_GND") (class "Default")
      (node (ref "*1") (pin "16") (pinfunction "SIM_GND_16") (pintype "power_in"))
      (node (ref "C70") (pin "1") (pinfunction "1_1") (pintype "passive"))
      (node (ref "C75") (pin "2") (pinfunction "2_2") (pintype "passive"))
      (node (ref "C77") (pin "1") (pinfunction "1_1") (pintype "passive"))
      (node (ref "C82") (pin "2") (pinfunction "2_2") (pintype "passive"))
      (node (ref "D8") (pin "1") (pinfunction "C1_1") (pintype "passive"))
      (node (ref "D9") (pin "1") (pinfunction "C1_1") (pintype "passive"))
      (node (ref "J5") (pin "C5") (pinfunction "GND_C5") (pintype "passive"))
      (node (ref "J6") (pin "C5") (pinfunction "GND_C5") (pintype "passive"))
    )
    (net (code "54") (name "unconnected-(*1-ADC-Pad6)") (class "Default")
      (node (ref "*1") (pin "6") (pinfunction "ADC_6") (pintype "input+no_connect"))
    )
    (net (code "55") (name "unconnected-(*1-CTS-Pad38)") (class "Default")
      (node (ref "*1") (pin "38") (pinfunction "CTS_38") (pintype "output+no_connect"))
    )
    (net (code "56") (name "unconnected-(*1-DBG_RXD-Pad30)") (class "Default")
      (node (ref "*1") (pin "30") (pinfunction "DBG_RXD_30") (pintype "input+no_connect"))
    )
    (net (code "57") (name "unconnected-(*1-DBG_TXD-Pad29)") (class "Default")
      (node (ref "*1") (pin "29") (pinfunction "DBG_TXD_29") (pintype "output+no_connect"))
    )
    (net (code "58") (name "unconnected-(*1-DCD-Pad36)") (class "Default")
      (node (ref "*1") (pin "36") (pinfunction "DCD_36") (pintype "output+no_connect"))
    )
    (net (code "59") (name "unconnected-(*1-LOUDSPKN-Pad53)") (class "Default")
      (node (ref "*1") (pin "53") (pinfunction "LOUDSPKN_53") (pintype "output+no_connect"))
    )
    (net (code "60") (name "unconnected-(*1-LOUDSPKP-Pad54)") (class "Default")
      (node (ref "*1") (pin "54") (pinfunction "LOUDSPKP_54") (pintype "output+no_connect"))
    )
    (net (code "61") (name "unconnected-(*1-MICN-Pad2)") (class "Default")
      (node (ref "*1") (pin "2") (pinfunction "MICN_2") (pintype "input+no_connect"))
    )
    (net (code "62") (name "unconnected-(*1-MICP-Pad1)") (class "Default")
      (node (ref "*1") (pin "1") (pinfunction "MICP_1") (pintype "input+no_connect"))
    )
    (net (code "63") (name "unconnected-(*1-PCM_CLK-Pad59)") (class "Default")
      (node (ref "*1") (pin "59") (pinfunction "PCM_CLK_59") (pintype "output+no_connect"))
    )
    (net (code "64") (name "unconnected-(*1-PCM_IN-Pad62)") (class "Default")
      (node (ref "*1") (pin "62") (pinfunction "PCM_IN_62") (pintype "input+no_connect"))
    )
    (net (code "65") (name "unconnected-(*1-PCM_OUT-Pad60)") (class "Default")
      (node (ref "*1") (pin "60") (pinfunction "PCM_OUT_60") (pintype "output+no_connect"))
    )
    (net (code "66") (name "unconnected-(*1-PCM_SYNC-Pad61)") (class "Default")
      (node (ref "*1") (pin "61") (pinfunction "PCM_SYNC_61") (pintype "output+no_connect"))
    )
    (net (code "67") (name "unconnected-(*1-RESERVED-Pad46)") (class "Default")
      (node (ref "*1") (pin "46") (pinfunction "RESERVED_46") (pintype "bidirectional+no_connect"))
    )
    (net (code "68") (name "unconnected-(*1-RESERVED-Pad55)") (class "Default")
      (node (ref "*1") (pin "55") (pinfunction "RESERVED_55") (pintype "bidirectional+no_connect"))
    )
    (net (code "69") (name "unconnected-(*1-RESERVED-Pad56)") (class "Default")
      (node (ref "*1") (pin "56") (pinfunction "RESERVED_56") (pintype "bidirectional+no_connect"))
    )
    (net (code "70") (name "unconnected-(*1-RESERVED-Pad57)") (class "Default")
      (node (ref "*1") (pin "57") (pinfunction "RESERVED_57") (pintype "bidirectional+no_connect"))
    )
    (net (code "71") (name "unconnected-(*1-RESERVED-Pad58)") (class "Default")
      (node (ref "*1") (pin "58") (pinfunction "RESERVED_58") (pintype "bidirectional+no_connect"))
    )
    (net (code "72") (name "unconnected-(*1-RESERVED-Pad63)") (class "Default")
      (node (ref "*1") (pin "63") (pinfunction "RESERVED_63") (pintype "bidirectional+no_connect"))
    )
    (net (code "73") (name "unconnected-(*1-RESERVED-Pad64)") (class "Default")
      (node (ref "*1") (pin "64") (pinfunction "RESERVED_64") (pintype "bidirectional+no_connect"))
    )
    (net (code "74") (name "unconnected-(*1-RESERVED-Pad65)") (class "Default")
      (node (ref "*1") (pin "65") (pinfunction "RESERVED_65") (pintype "bidirectional+no_connect"))
    )
    (net (code "75") (name "unconnected-(*1-RESERVED-Pad66)") (class "Default")
      (node (ref "*1") (pin "66") (pinfunction "RESERVED_66") (pintype "bidirectional+no_connect"))
    )
    (net (code "76") (name "unconnected-(*1-RESERVED-Pad67)") (class "Default")
      (node (ref "*1") (pin "67") (pinfunction "RESERVED_67") (pintype "bidirectional+no_connect"))
    )
    (net (code "77") (name "unconnected-(*1-RESERVED-Pad68)") (class "Default")
      (node (ref "*1") (pin "68") (pinfunction "RESERVED_68") (pintype "bidirectional+no_connect"))
    )
    (net (code "78") (name "unconnected-(*1-RTS-Pad39)") (class "Default")
      (node (ref "*1") (pin "39") (pinfunction "RTS_39") (pintype "input+no_connect"))
    )
    (net (code "79") (name "unconnected-(*1-SD_CLK-Pad8)") (class "Default")
      (node (ref "*1") (pin "8") (pinfunction "SD_CLK_8") (pintype "output+no_connect"))
    )
    (net (code "80") (name "unconnected-(*1-SD_CMD-Pad7)") (class "Default")
      (node (ref "*1") (pin "7") (pinfunction "SD_CMD_7") (pintype "output+no_connect"))
    )
    (net (code "81") (name "unconnected-(*1-SD_DATA-Pad9)") (class "Default")
      (node (ref "*1") (pin "9") (pinfunction "SD_DATA_9") (pintype "bidirectional+no_connect"))
    )
    (net (code "82") (name "unconnected-(*1-SPKN-Pad4)") (class "Default")
      (node (ref "*1") (pin "4") (pinfunction "SPKN_4") (pintype "output+no_connect"))
    )
    (net (code "83") (name "unconnected-(*1-SPKP-Pad3)") (class "Default")
      (node (ref "*1") (pin "3") (pinfunction "SPKP_3") (pintype "output+no_connect"))
    )
    (net (code "84") (name "unconnected-(*1-VDD_EXT-Pad43)") (class "Default")
      (node (ref "*1") (pin "43") (pinfunction "VDD_EXT_43") (pintype "power_in+no_connect"))
    )
    (net (code "85") (name "unconnected-(J5-VPP-PadC6)") (class "Default")
      (node (ref "J5") (pin "C6") (pinfunction "VPP_C6") (pintype "passive+no_connect"))
    )
    (net (code "86") (name "unconnected-(J6-VPP-PadC6)") (class "Default")
      (node (ref "J6") (pin "C6") (pinfunction "VPP_C6") (pintype "passive+no_connect"))
    )
  )
)
